# AutomationSystem-Schematic_2022-08-13.net
KiCad netlist of a schematic drawn in Altium Designer
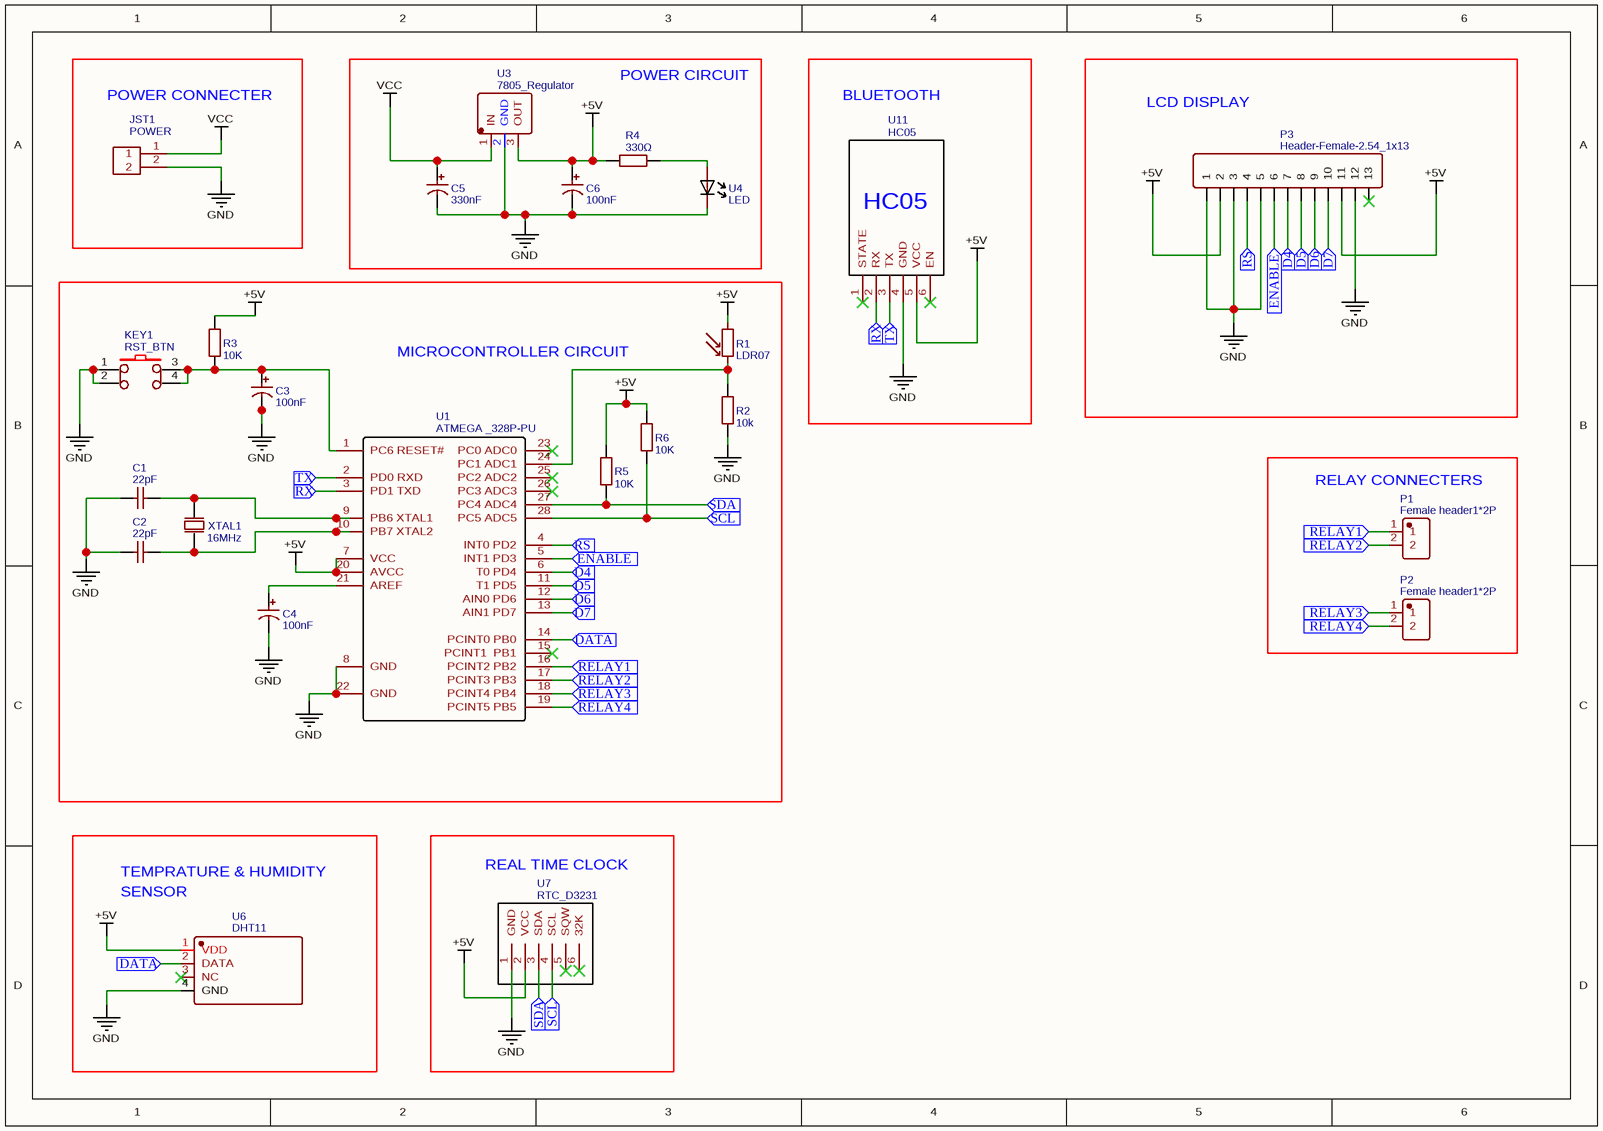
[diagram p0: AutomationSystem-Schematic_2022-08-13.schdoc]

(export (version "E")
  (design (tool "Eeschema 10.0.6"))
  (components
    (comp (ref "C1")
      (value "22pF")
      (fields
        (field (name "BOM_MANUFACTURER PART") "22pf/50V 10%")
        (field (name "BOM_SUPPLIER PART") "C9316")
      )
      (libsource (lib "altium-import") (part "root_0_22pF_"))
    )
    (comp (ref "C2")
      (value "22pF")
      (fields
        (field (name "BOM_MANUFACTURER PART") "22pf/50V 10%")
        (field (name "BOM_SUPPLIER PART") "C9316")
      )
      (libsource (lib "altium-import") (part "root_0_22pF_"))
    )
    (comp (ref "C3")
      (value "100nF")
      (fields (field (name "BOM_MANUFACTURER PART") "0.1UF 50V") (field (name "BOM_SUPPLIER PART") "C28061"))
      (libsource (lib "altium-import") (part "root_0_100nF_"))
    )
    (comp (ref "C4")
      (value "100nF")
      (fields (field (name "BOM_MANUFACTURER PART") "0.1UF 50V") (field (name "BOM_SUPPLIER PART") "C28061"))
      (libsource (lib "altium-import") (part "root_0_100nF_"))
    )
    (comp (ref "C5")
      (value "330nF")
      (fields
        (field (name "BOM_MANUFACTURER PART") "0.33uF 50V 5*11")
        (field (name "BOM_SUPPLIER PART") "C45097")
      )
      (libsource (lib "altium-import") (part "root_0_330nF_"))
    )
    (comp (ref "C6")
      (value "100nF")
      (fields (field (name "BOM_MANUFACTURER PART") "0.1UF 50V") (field (name "BOM_SUPPLIER PART") "C28061"))
      (libsource (lib "altium-import") (part "root_0_100nF_"))
    )
    (comp (ref "JST1")
      (value "POWER")
      (fields
        (field (name "BOM_MANUFACTURER PART") "XHB-2A Connector")
        (field (name "BOM_SUPPLIER PART") "C57981")
      )
      (libsource (lib "altium-import") (part "root_0_POWER_"))
    )
    (comp (ref "KEY1")
      (value "RST_BTN")
      (fields
        (field (name "BOM_SUPPLIER PART") "C59980")
        (field (name "BOM_MANUFACTURER PART") "button6*6*8.5")
      )
      (libsource (lib "altium-import") (part "root_0_RST_BTN_"))
    )
    (comp (ref "P1")
      (value "Female header1*2P")
      (fields (field (name "BOM_SUPPLIER PART") "C66509"))
      (libsource (lib "altium-import") (part "root_0_Female header1*2P_"))
    )
    (comp (ref "P2")
      (value "Female header1*2P")
      (fields (field (name "BOM_SUPPLIER PART") "C66509"))
      (libsource (lib "altium-import") (part "root_0_Female header1*2P_"))
    )
    (comp (ref "P3")
      (value "Header-Female-2.54_1x13")
      (fields
        (field (name "BOM_MANUFACTURER PART") "Female header 2.54-1*13P")
        (field (name "BOM_SUPPLIER PART") "C52709")
      )
      (libsource (lib "altium-import") (part "root_1_Header-Female-2.54_1x13_"))
    )
    (comp (ref "R1")
      (value "LDR07")
      (fields (field (name "CONTRIBUTOR") "KiCAD"))
      (libsource (lib "altium-import") (part "root_0_LDR07_"))
    )
    (comp (ref "R2")
      (value "10k")
      (fields
        (field (name "POWER") "1/4W")
        (field (name "TOLERANCE") "±1%")
        (field (name "BOM_SUPPLIER PART") "E57439")
      )
      (libsource (lib "altium-import") (part "root_1_10k_"))
    )
    (comp (ref "R3")
      (value "10K")
      (fields
        (field (name "POWER") "1/4W")
        (field (name "TOLERANCE") "±1%")
        (field (name "BOM_SUPPLIER PART") "E57439")
      )
      (libsource (lib "altium-import") (part "root_1_10K_"))
    )
    (comp (ref "R4")
      (value "330Ω")
      (fields
        (field (name "POWER") "1/4W")
        (field (name "TOLERANCE") "±1%")
        (field (name "BOM_SUPPLIER PART") "E57439")
      )
      (libsource (lib "altium-import") (part "root_0_330Ω_"))
    )
    (comp (ref "R5")
      (value "10K")
      (fields
        (field (name "POWER") "1/4W")
        (field (name "TOLERANCE") "±1%")
        (field (name "BOM_SUPPLIER PART") "E57439")
      )
      (libsource (lib "altium-import") (part "root_1_10K_"))
    )
    (comp (ref "R6")
      (value "10K")
      (fields
        (field (name "POWER") "1/4W")
        (field (name "TOLERANCE") "±1%")
        (field (name "BOM_SUPPLIER PART") "E57439")
      )
      (libsource (lib "altium-import") (part "root_1_10K_"))
    )
    (comp (ref "U1")
      (value "ATMEGA _328P-PU")
      (fields
        (field (name "BOM_MANUFACTURER PART") "ATMEGA328P-PU")
        (field (name "BOM_SUPPLIER PART") "C33901")
        (field (name "CONTRIBUTOR") "LCSC")
      )
      (libsource (lib "altium-import") (part "root_0_ATMEGA _328P-PU_"))
    )
    (comp (ref "U3")
      (value "7805_Regulator")
      (fields
        (field (name "BOM_SUPPLIER PART") "C305416")
        (field (name "BOM_MANUFACTURER PART") "7805")
        (field (name "CONTRIBUTOR") "LCSC")
      )
      (libsource (lib "altium-import") (part "root_1_7805_Regulator_"))
    )
    (comp (ref "U4")
      (value "LED")
      (fields (field (name "BOM_MANUFACTURER PART") "5mm LED") (field (name "CONTRIBUTOR") "Axbri"))
      (libsource (lib "altium-import") (part "root_3_LED_"))
    )
    (comp (ref "U6")
      (value "DHT11")
      (fields (field (name "BOM_SUPPLIER PART") "C117051") (field (name "CONTRIBUTOR") "LCSC"))
      (libsource (lib "altium-import") (part "root_0_DHT11_"))
    )
    (comp (ref "U7")
      (value "RTC_D3231")
      (fields (field (name "CONTRIBUTOR") "tim_hcs"))
      (libsource (lib "altium-import") (part "root_0_RTC_D3231_"))
    )
    (comp (ref "U11")
      (value "HC05")
      (fields (field (name "CONTRIBUTOR") "marciofaccin"))
      (libsource (lib "altium-import") (part "root_0_HC05_"))
    )
    (comp (ref "XTAL1")
      (value "16MHz")
      (fields
        (field (name "BOM_MANUFACTURER PART") "0SC-16MHz")
        (field (name "CONTRIBUTOR") "Mantas Petrauskas")
      )
      (libsource (lib "altium-import") (part "root_1_16MHz_"))
    )
  )
  (nets
    (net (code "1") (name "+5V") (class "Default")
      (node (ref "C6") (pin "1") (pinfunction "1_1") (pintype "passive"))
      (node (ref "P3") (pin "11") (pinfunction "11_11") (pintype "passive"))
      (node (ref "P3") (pin "2") (pinfunction "2_2") (pintype "passive"))
      (node (ref "R1") (pin "1") (pintype "passive"))
      (node (ref "R3") (pin "2") (pinfunction "2_2") (pintype "passive"))
      (node (ref "R4") (pin "1") (pinfunction "1_1") (pintype "passive"))
      (node (ref "R5") (pin "2") (pinfunction "2_2") (pintype "passive"))
      (node (ref "R6") (pin "2") (pinfunction "2_2") (pintype "passive"))
      (node (ref "U1") (pin "20") (pinfunction "AVCC_20") (pintype "passive"))
      (node (ref "U1") (pin "7") (pinfunction "VCC_7") (pintype "passive"))
      (node (ref "U11") (pin "5") (pinfunction "VCC_5") (pintype "passive"))
      (node (ref "U3") (pin "3") (pinfunction "OUT_3") (pintype "passive"))
      (node (ref "U6") (pin "1") (pinfunction "VDD_1") (pintype "passive"))
      (node (ref "U7") (pin "2") (pinfunction "VCC_2") (pintype "passive"))
    )
    (net (code "2") (name "/D4") (class "Default")
      (node (ref "P3") (pin "7") (pinfunction "7_7") (pintype "passive"))
      (node (ref "U1") (pin "6") (pinfunction "T0_PD4_6") (pintype "passive"))
    )
    (net (code "3") (name "/D5") (class "Default")
      (node (ref "P3") (pin "8") (pinfunction "8_8") (pintype "passive"))
      (node (ref "U1") (pin "11") (pinfunction "T1_PD5_11") (pintype "passive"))
    )
    (net (code "4") (name "/D6") (class "Default")
      (node (ref "P3") (pin "9") (pinfunction "9_9") (pintype "passive"))
      (node (ref "U1") (pin "12") (pinfunction "AIN0_PD6_12") (pintype "passive"))
    )
    (net (code "5") (name "/D7") (class "Default")
      (node (ref "P3") (pin "10") (pinfunction "10_10") (pintype "passive"))
      (node (ref "U1") (pin "13") (pinfunction "AIN1_PD7_13") (pintype "passive"))
    )
    (net (code "6") (name "/DATA") (class "Default")
      (node (ref "U1") (pin "14") (pinfunction "PCINT0_PB0_14") (pintype "passive"))
      (node (ref "U6") (pin "2") (pinfunction "DATA_2") (pintype "passive"))
    )
    (net (code "7") (name "/ENABLE") (class "Default")
      (node (ref "P3") (pin "6") (pinfunction "6_6") (pintype "passive"))
      (node (ref "U1") (pin "5") (pinfunction "INT1_PD3_5") (pintype "passive"))
    )
    (net (code "8") (name "/RELAY1") (class "Default")
      (node (ref "P1") (pin "1") (pinfunction "1_1") (pintype "passive"))
      (node (ref "U1") (pin "16") (pinfunction "PCINT2_PB2_16") (pintype "passive"))
    )
    (net (code "9") (name "/RELAY2") (class "Default")
      (node (ref "P1") (pin "2") (pinfunction "2_2") (pintype "passive"))
      (node (ref "U1") (pin "17") (pinfunction "PCINT3_PB3_17") (pintype "passive"))
    )
    (net (code "10") (name "/RELAY3") (class "Default")
      (node (ref "P2") (pin "1") (pinfunction "1_1") (pintype "passive"))
      (node (ref "U1") (pin "18") (pinfunction "PCINT4_PB4_18") (pintype "passive"))
    )
    (net (code "11") (name "/RELAY4") (class "Default")
      (node (ref "P2") (pin "2") (pinfunction "2_2") (pintype "passive"))
      (node (ref "U1") (pin "19") (pinfunction "PCINT5_PB5_19") (pintype "passive"))
    )
    (net (code "12") (name "/RS") (class "Default")
      (node (ref "P3") (pin "4") (pinfunction "4_4") (pintype "passive"))
      (node (ref "U1") (pin "4") (pinfunction "INT0_PD2_4") (pintype "passive"))
    )
    (net (code "13") (name "/RX") (class "Default")
      (node (ref "U1") (pin "3") (pinfunction "PD1_TXD_3") (pintype "passive"))
      (node (ref "U11") (pin "2") (pinfunction "RX_2") (pintype "passive"))
    )
    (net (code "14") (name "/SCL") (class "Default")
      (node (ref "R6") (pin "1") (pinfunction "1_1") (pintype "passive"))
      (node (ref "U1") (pin "28") (pinfunction "PC5_ADC5_28") (pintype "passive"))
      (node (ref "U7") (pin "4") (pinfunction "SCL_4") (pintype "passive"))
    )
    (net (code "15") (name "/SDA") (class "Default")
      (node (ref "R5") (pin "1") (pinfunction "1_1") (pintype "passive"))
      (node (ref "U1") (pin "27") (pinfunction "PC4_ADC4_27") (pintype "passive"))
      (node (ref "U7") (pin "3") (pinfunction "SDA_3") (pintype "passive"))
    )
    (net (code "16") (name "/TX") (class "Default")
      (node (ref "U1") (pin "2") (pinfunction "PD0_RXD_2") (pintype "passive"))
      (node (ref "U11") (pin "3") (pinfunction "TX_3") (pintype "passive"))
    )
    (net (code "17") (name "GND") (class "Default")
      (node (ref "C1") (pin "1") (pinfunction "1_1") (pintype "passive"))
      (node (ref "C2") (pin "1") (pinfunction "1_1") (pintype "passive"))
      (node (ref "C3") (pin "2") (pinfunction "2_2") (pintype "passive"))
      (node (ref "C4") (pin "2") (pinfunction "2_2") (pintype "passive"))
      (node (ref "C5") (pin "2") (pinfunction "2_2") (pintype "passive"))
      (node (ref "C6") (pin "2") (pinfunction "2_2") (pintype "passive"))
      (node (ref "JST1") (pin "2") (pinfunction "2_2") (pintype "passive"))
      (node (ref "KEY1") (pin "1") (pinfunction "1_1") (pintype "passive"))
      (node (ref "KEY1") (pin "2") (pinfunction "2_2") (pintype "passive"))
      (node (ref "P3") (pin "1") (pinfunction "1_1") (pintype "passive"))
      (node (ref "P3") (pin "12") (pinfunction "12_12") (pintype "passive"))
      (node (ref "P3") (pin "3") (pinfunction "3_3") (pintype "passive"))
      (node (ref "P3") (pin "5") (pinfunction "5_5") (pintype "passive"))
      (node (ref "R2") (pin "1") (pinfunction "1_1") (pintype "passive"))
      (node (ref "U1") (pin "22") (pinfunction "GND_22") (pintype "passive"))
      (node (ref "U1") (pin "8") (pinfunction "GND_8") (pintype "passive"))
      (node (ref "U11") (pin "4") (pinfunction "GND_4") (pintype "passive"))
      (node (ref "U3") (pin "2") (pinfunction "GND_2") (pintype "passive"))
      (node (ref "U4") (pin "2") (pinfunction "2_2") (pintype "passive"))
      (node (ref "U6") (pin "4") (pinfunction "GND_4") (pintype "passive"))
      (node (ref "U7") (pin "1") (pinfunction "GND_1") (pintype "passive"))
    )
    (net (code "18") (name "Net-(R4-Pad2)") (class "Default")
      (node (ref "R4") (pin "2") (pinfunction "2_2") (pintype "passive"))
      (node (ref "U4") (pin "1") (pinfunction "1_1") (pintype "passive"))
    )
    (net (code "19") (name "Net-(U1-AREF)") (class "Default")
      (node (ref "C4") (pin "1") (pinfunction "1_1") (pintype "passive"))
      (node (ref "U1") (pin "21") (pinfunction "AREF_21") (pintype "passive"))
    )
    (net (code "20") (name "Net-(U1-PB6_XTAL1)") (class "Default")
      (node (ref "C1") (pin "2") (pinfunction "2_2") (pintype "passive"))
      (node (ref "U1") (pin "9") (pinfunction "PB6_XTAL1_9") (pintype "passive"))
      (node (ref "XTAL1") (pin "1") (pinfunction "OSC1_1") (pintype "passive"))
    )
    (net (code "21") (name "Net-(U1-PB7_XTAL2)") (class "Default")
      (node (ref "C2") (pin "2") (pinfunction "2_2") (pintype "passive"))
      (node (ref "U1") (pin "10") (pinfunction "PB7_XTAL2_10") (pintype "passive"))
      (node (ref "XTAL1") (pin "2") (pinfunction "OSC2_2") (pintype "passive"))
    )
    (net (code "22") (name "Net-(U1-PC1_ADC1)") (class "Default")
      (node (ref "R1") (pin "2") (pintype "passive"))
      (node (ref "R2") (pin "2") (pinfunction "2_2") (pintype "passive"))
      (node (ref "U1") (pin "24") (pinfunction "PC1_ADC1_24") (pintype "passive"))
    )
    (net (code "23") (name "Net-(U1-PC6_RESET#)") (class "Default")
      (node (ref "C3") (pin "1") (pinfunction "1_1") (pintype "passive"))
      (node (ref "KEY1") (pin "3") (pinfunction "3_3") (pintype "passive"))
      (node (ref "KEY1") (pin "4") (pinfunction "4_4") (pintype "passive"))
      (node (ref "R3") (pin "1") (pinfunction "1_1") (pintype "passive"))
      (node (ref "U1") (pin "1") (pinfunction "PC6_RESET#_1") (pintype "passive"))
    )
    (net (code "24") (name "VCC") (class "Default")
      (node (ref "C5") (pin "1") (pinfunction "1_1") (pintype "passive"))
      (node (ref "JST1") (pin "1") (pinfunction "1_1") (pintype "passive"))
      (node (ref "U3") (pin "1") (pinfunction "IN_1") (pintype "passive"))
    )
    (net (code "25") (name "unconnected-(P3-Pad13)") (class "Default")
      (node (ref "P3") (pin "13") (pinfunction "13_13") (pintype "passive+no_connect"))
    )
    (net (code "26") (name "unconnected-(U1-PC0_ADC0-Pad23)") (class "Default")
      (node (ref "U1") (pin "23") (pinfunction "PC0_ADC0_23") (pintype "passive+no_connect"))
    )
    (net (code "27") (name "unconnected-(U1-PC2_ADC2-Pad25)") (class "Default")
      (node (ref "U1") (pin "25") (pinfunction "PC2_ADC2_25") (pintype "passive+no_connect"))
    )
    (net (code "28") (name "unconnected-(U1-PC3_ADC3-Pad26)") (class "Default")
      (node (ref "U1") (pin "26") (pinfunction "PC3_ADC3_26") (pintype "passive+no_connect"))
    )
    (net (code "29") (name "unconnected-(U1-PCINT1__PB1-Pad15)") (class "Default")
      (node (ref "U1") (pin "15") (pinfunction "PCINT1__PB1_15") (pintype "passive+no_connect"))
    )
    (net (code "30") (name "unconnected-(U6-NC-Pad3)") (class "Default")
      (node (ref "U6") (pin "3") (pinfunction "NC_3") (pintype "passive+no_connect"))
    )
    (net (code "31") (name "unconnected-(U7-32K-Pad6)") (class "Default")
      (node (ref "U7") (pin "6") (pinfunction "32K_6") (pintype "passive+no_connect"))
    )
    (net (code "32") (name "unconnected-(U7-SQW-Pad5)") (class "Default")
      (node (ref "U7") (pin "5") (pinfunction "SQW_5") (pintype "passive+no_connect"))
    )
    (net (code "33") (name "unconnected-(U11-EN-Pad6)") (class "Default")
      (node (ref "U11") (pin "6") (pinfunction "EN_6") (pintype "passive+no_connect"))
    )
    (net (code "34") (name "unconnected-(U11-STATE-Pad1)") (class "Default")
      (node (ref "U11") (pin "1") (pinfunction "STATE_1") (pintype "passive+no_connect"))
    )
  )
)
